# untitled.net
KiCad netlist of a schematic drawn in EAGLE
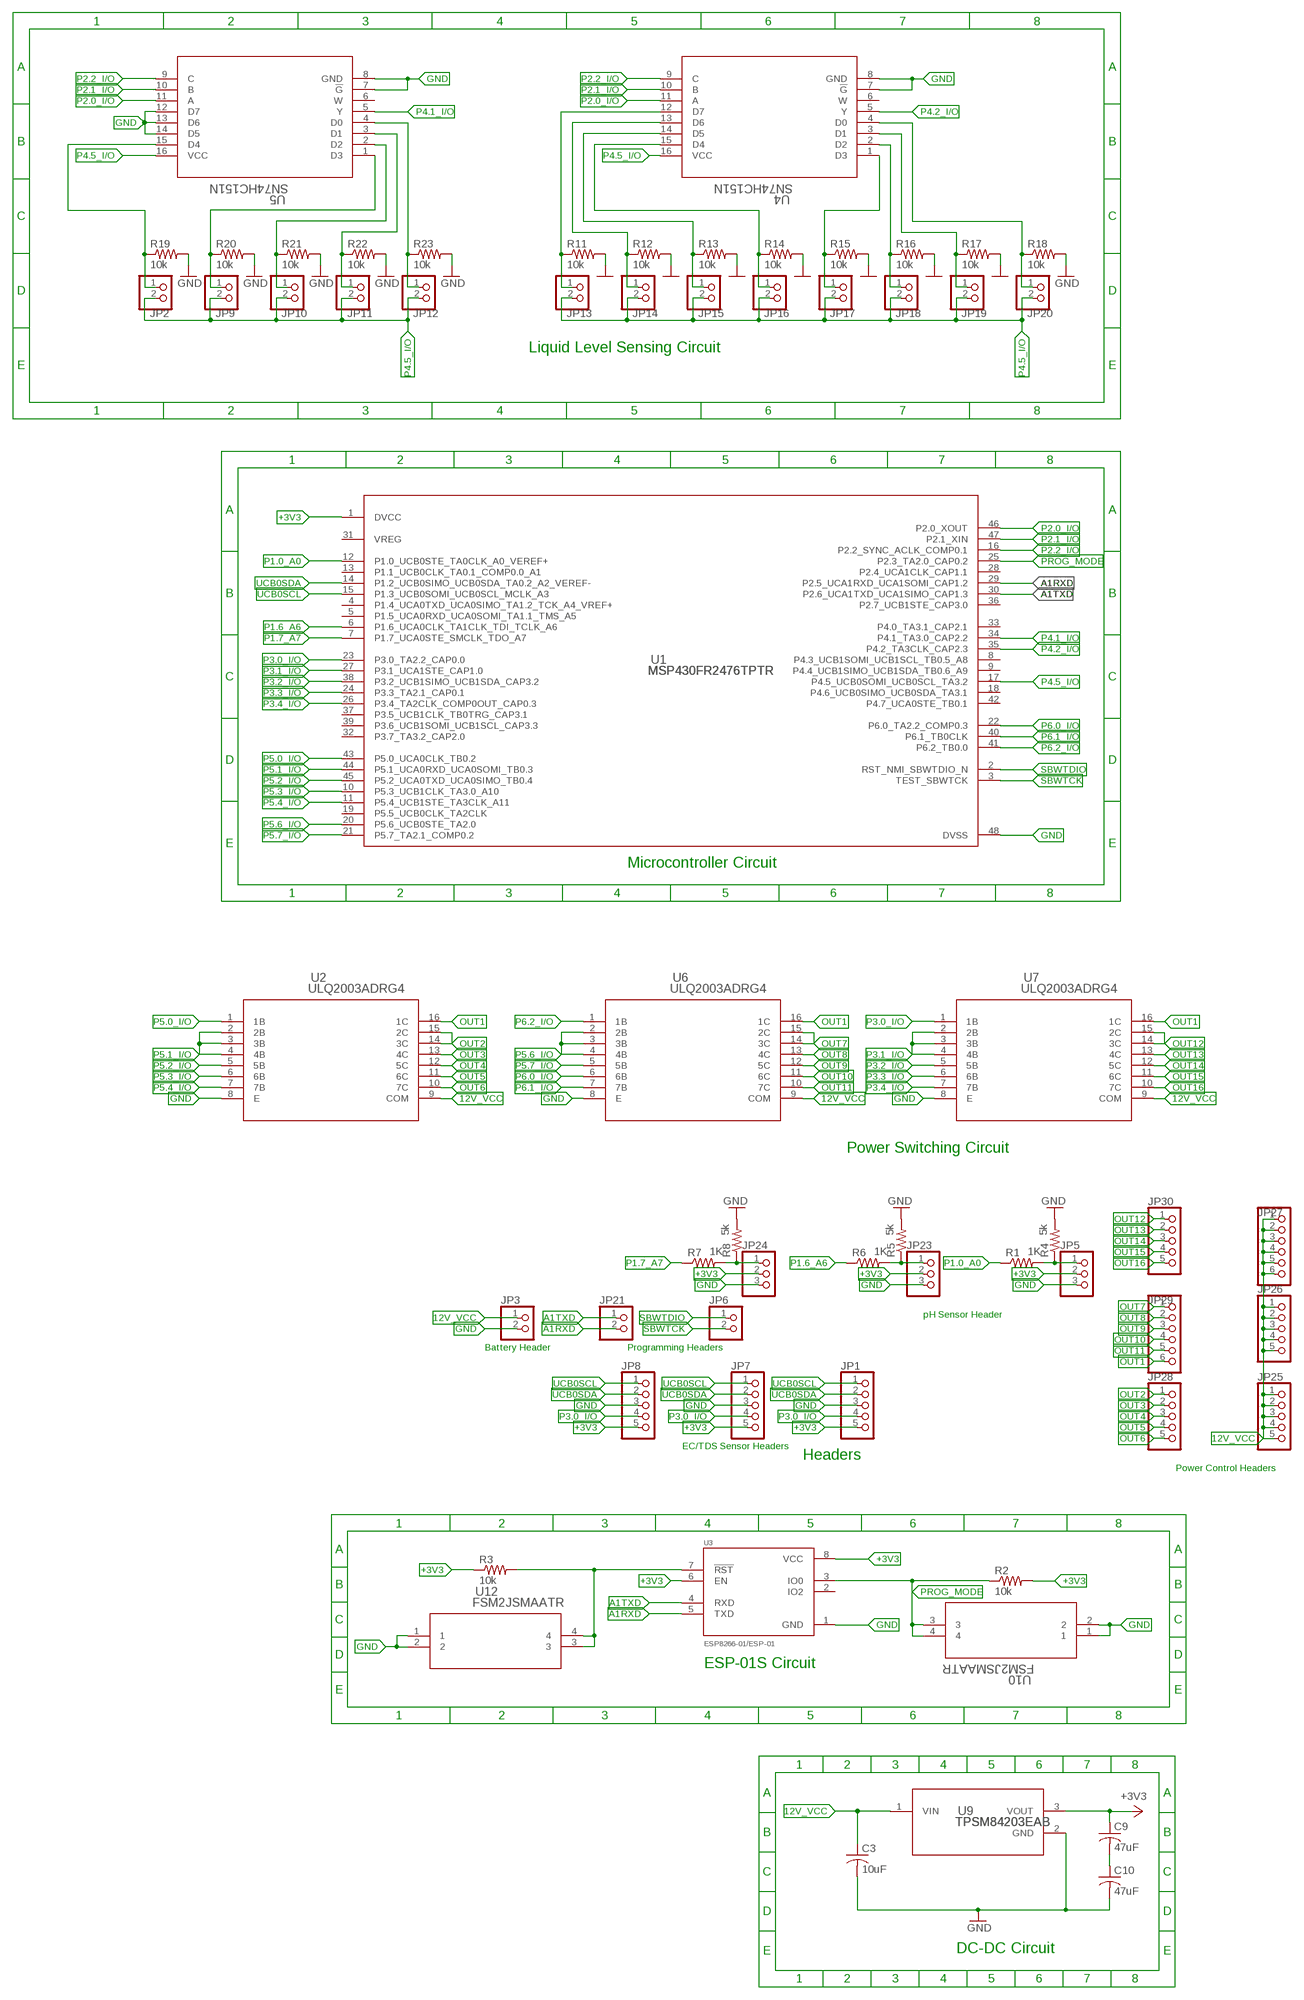
[diagram p0: schematic, sheet 1]

(export (version "E")
  (design (tool "Eeschema 10.0.6"))
  (components
    (comp (ref "C3")
      (value "10uF")
      (footprint "eagle-import:C1206")
      (libsource (lib "eagle-import") (part "C-USC1206"))
    )
    (comp (ref "C9")
      (value "47uF")
      (footprint "eagle-import:C1206")
      (libsource (lib "eagle-import") (part "C-USC1206"))
    )
    (comp (ref "C10")
      (value "47uF")
      (footprint "eagle-import:C1206")
      (libsource (lib "eagle-import") (part "C-USC1206"))
    )
    (comp (ref "JP1")
      (value "PINHD-1X5")
      (footprint "eagle-import:1X05")
      (libsource (lib "eagle-import") (part "PINHD-1X5"))
    )
    (comp (ref "JP2")
      (value "PINHD-1X2")
      (footprint "eagle-import:1X02")
      (libsource (lib "eagle-import") (part "PINHD-1X2"))
    )
    (comp (ref "JP3")
      (value "PINHD-1X2")
      (footprint "eagle-import:1X02")
      (libsource (lib "eagle-import") (part "PINHD-1X2"))
    )
    (comp (ref "JP5")
      (value "PINHD-1X3")
      (footprint "eagle-import:1X03")
      (libsource (lib "eagle-import") (part "PINHD-1X3"))
    )
    (comp (ref "JP6")
      (value "PINHD-1X2")
      (footprint "eagle-import:1X02")
      (libsource (lib "eagle-import") (part "PINHD-1X2"))
    )
    (comp (ref "JP7")
      (value "PINHD-1X5")
      (footprint "eagle-import:1X05")
      (libsource (lib "eagle-import") (part "PINHD-1X5"))
    )
    (comp (ref "JP8")
      (value "PINHD-1X5")
      (footprint "eagle-import:1X05")
      (libsource (lib "eagle-import") (part "PINHD-1X5"))
    )
    (comp (ref "JP9")
      (value "PINHD-1X2")
      (footprint "eagle-import:1X02")
      (libsource (lib "eagle-import") (part "PINHD-1X2"))
    )
    (comp (ref "JP10")
      (value "PINHD-1X2")
      (footprint "eagle-import:1X02")
      (libsource (lib "eagle-import") (part "PINHD-1X2"))
    )
    (comp (ref "JP11")
      (value "PINHD-1X2")
      (footprint "eagle-import:1X02")
      (libsource (lib "eagle-import") (part "PINHD-1X2"))
    )
    (comp (ref "JP12")
      (value "PINHD-1X2")
      (footprint "eagle-import:1X02")
      (libsource (lib "eagle-import") (part "PINHD-1X2"))
    )
    (comp (ref "JP13")
      (value "PINHD-1X2")
      (footprint "eagle-import:1X02")
      (libsource (lib "eagle-import") (part "PINHD-1X2"))
    )
    (comp (ref "JP14")
      (value "PINHD-1X2")
      (footprint "eagle-import:1X02")
      (libsource (lib "eagle-import") (part "PINHD-1X2"))
    )
    (comp (ref "JP15")
      (value "PINHD-1X2")
      (footprint "eagle-import:1X02")
      (libsource (lib "eagle-import") (part "PINHD-1X2"))
    )
    (comp (ref "JP16")
      (value "PINHD-1X2")
      (footprint "eagle-import:1X02")
      (libsource (lib "eagle-import") (part "PINHD-1X2"))
    )
    (comp (ref "JP17")
      (value "PINHD-1X2")
      (footprint "eagle-import:1X02")
      (libsource (lib "eagle-import") (part "PINHD-1X2"))
    )
    (comp (ref "JP18")
      (value "PINHD-1X2")
      (footprint "eagle-import:1X02")
      (libsource (lib "eagle-import") (part "PINHD-1X2"))
    )
    (comp (ref "JP19")
      (value "PINHD-1X2")
      (footprint "eagle-import:1X02")
      (libsource (lib "eagle-import") (part "PINHD-1X2"))
    )
    (comp (ref "JP20")
      (value "PINHD-1X2")
      (footprint "eagle-import:1X02")
      (libsource (lib "eagle-import") (part "PINHD-1X2"))
    )
    (comp (ref "JP21")
      (value "PINHD-1X2")
      (footprint "eagle-import:1X02")
      (libsource (lib "eagle-import") (part "PINHD-1X2"))
    )
    (comp (ref "JP23")
      (value "PINHD-1X3")
      (footprint "eagle-import:1X03")
      (libsource (lib "eagle-import") (part "PINHD-1X3"))
    )
    (comp (ref "JP24")
      (value "PINHD-1X3")
      (footprint "eagle-import:1X03")
      (libsource (lib "eagle-import") (part "PINHD-1X3"))
    )
    (comp (ref "JP25")
      (value "PINHD-1X5")
      (footprint "eagle-import:1X05")
      (libsource (lib "eagle-import") (part "PINHD-1X5"))
    )
    (comp (ref "JP26")
      (value "PINHD-1X5")
      (footprint "eagle-import:1X05")
      (libsource (lib "eagle-import") (part "PINHD-1X5"))
    )
    (comp (ref "JP27")
      (value "PINHD-1X6")
      (footprint "eagle-import:1X06")
      (libsource (lib "eagle-import") (part "PINHD-1X6"))
    )
    (comp (ref "JP28")
      (value "PINHD-1X5")
      (footprint "eagle-import:1X05")
      (libsource (lib "eagle-import") (part "PINHD-1X5"))
    )
    (comp (ref "JP29")
      (value "PINHD-1X6")
      (footprint "eagle-import:1X06")
      (libsource (lib "eagle-import") (part "PINHD-1X6"))
    )
    (comp (ref "JP30")
      (value "PINHD-1X5")
      (footprint "eagle-import:1X05")
      (libsource (lib "eagle-import") (part "PINHD-1X5"))
    )
    (comp (ref "R1")
      (value "1K")
      (footprint "eagle-import:R1206")
      (libsource (lib "eagle-import") (part "R-US_R1206"))
    )
    (comp (ref "R2")
      (value "10k")
      (footprint "eagle-import:R1206")
      (libsource (lib "eagle-import") (part "R-US_R1206"))
    )
    (comp (ref "R3")
      (value "10k")
      (footprint "eagle-import:R1206")
      (libsource (lib "eagle-import") (part "R-US_R1206"))
    )
    (comp (ref "R4")
      (value "5k")
      (footprint "eagle-import:R1206")
      (libsource (lib "eagle-import") (part "R-US_R1206"))
    )
    (comp (ref "R5")
      (value "5k")
      (footprint "eagle-import:R1206")
      (libsource (lib "eagle-import") (part "R-US_R1206"))
    )
    (comp (ref "R6")
      (value "1K")
      (footprint "eagle-import:R1206")
      (libsource (lib "eagle-import") (part "R-US_R1206"))
    )
    (comp (ref "R7")
      (value "1K")
      (footprint "eagle-import:R1206")
      (libsource (lib "eagle-import") (part "R-US_R1206"))
    )
    (comp (ref "R8")
      (value "5k")
      (footprint "eagle-import:R1206")
      (libsource (lib "eagle-import") (part "R-US_R1206"))
    )
    (comp (ref "R11")
      (value "10k")
      (footprint "eagle-import:R1206")
      (libsource (lib "eagle-import") (part "R-US_R1206"))
    )
    (comp (ref "R12")
      (value "10k")
      (footprint "eagle-import:R1206")
      (libsource (lib "eagle-import") (part "R-US_R1206"))
    )
    (comp (ref "R13")
      (value "10k")
      (footprint "eagle-import:R1206")
      (libsource (lib "eagle-import") (part "R-US_R1206"))
    )
    (comp (ref "R14")
      (value "10k")
      (footprint "eagle-import:R1206")
      (libsource (lib "eagle-import") (part "R-US_R1206"))
    )
    (comp (ref "R15")
      (value "10k")
      (footprint "eagle-import:R1206")
      (libsource (lib "eagle-import") (part "R-US_R1206"))
    )
    (comp (ref "R16")
      (value "10k")
      (footprint "eagle-import:R1206")
      (libsource (lib "eagle-import") (part "R-US_R1206"))
    )
    (comp (ref "R17")
      (value "10k")
      (footprint "eagle-import:R1206")
      (libsource (lib "eagle-import") (part "R-US_R1206"))
    )
    (comp (ref "R18")
      (value "10k")
      (footprint "eagle-import:R1206")
      (libsource (lib "eagle-import") (part "R-US_R1206"))
    )
    (comp (ref "R19")
      (value "10k")
      (footprint "eagle-import:R1206")
      (libsource (lib "eagle-import") (part "R-US_R1206"))
    )
    (comp (ref "R20")
      (value "10k")
      (footprint "eagle-import:R1206")
      (libsource (lib "eagle-import") (part "R-US_R1206"))
    )
    (comp (ref "R21")
      (value "10k")
      (footprint "eagle-import:R1206")
      (libsource (lib "eagle-import") (part "R-US_R1206"))
    )
    (comp (ref "R22")
      (value "10k")
      (footprint "eagle-import:R1206")
      (libsource (lib "eagle-import") (part "R-US_R1206"))
    )
    (comp (ref "R23")
      (value "10k")
      (footprint "eagle-import:R1206")
      (libsource (lib "eagle-import") (part "R-US_R1206"))
    )
    (comp (ref "U1")
      (value "MSP430FR2476TPTR")
      (footprint "eagle-import:PT0048A_N")
      (fields (field (name "COPYRIGHT") "Copyright (C) 2023 Ultra Librarian. All rights reserved."))
      (libsource (lib "eagle-import") (part "MSP430FR2476TPTR"))
    )
    (comp (ref "U2")
      (value "ULQ2003ADRG4")
      (footprint "eagle-import:D16")
      (fields (field (name "COPYRIGHT") "Copyright (C) 2023 Ultra Librarian. All rights reserved."))
      (libsource (lib "eagle-import") (part "ULQ2003ADRG4"))
    )
    (comp (ref "U3")
      (value "ESP8266-01/ESP-01")
      (footprint "eagle-import:XCVR_ESP8266-01_ESP-01")
      (fields (field (name "MF") "AI-Thinker"))
      (libsource (lib "eagle-import") (part "ESP8266-01/ESP-01"))
    )
    (comp (ref "U4")
      (value "SN74HC151N")
      (footprint "eagle-import:N16")
      (fields (field (name "COPYRIGHT") "Copyright (C) 2022 Ultra Librarian. All rights reserved."))
      (libsource (lib "eagle-import") (part "SN74HC151N"))
    )
    (comp (ref "U5")
      (value "SN74HC151N")
      (footprint "eagle-import:N16")
      (fields (field (name "COPYRIGHT") "Copyright (C) 2022 Ultra Librarian. All rights reserved."))
      (libsource (lib "eagle-import") (part "SN74HC151N"))
    )
    (comp (ref "U6")
      (value "ULQ2003ADRG4")
      (footprint "eagle-import:D16")
      (fields
        (field (name "SPICEPREFIX") "X")
        (field (name "COPYRIGHT") "Copyright (C) 2023 Ultra Librarian. All rights reserved.")
      )
      (libsource (lib "eagle-import") (part "ULQ2003ADRG4"))
    )
    (comp (ref "U7")
      (value "ULQ2003ADRG4")
      (footprint "eagle-import:D16")
      (fields
        (field (name "SPICEPREFIX") "X")
        (field (name "COPYRIGHT") "Copyright (C) 2023 Ultra Librarian. All rights reserved.")
      )
      (libsource (lib "eagle-import") (part "ULQ2003ADRG4"))
    )
    (comp (ref "U9")
      (value "TPSM84203EAB")
      (footprint "eagle-import:EAB0003A")
      (fields (field (name "COPYRIGHT") "Copyright (C) 2023 Ultra Librarian. All rights reserved."))
      (libsource (lib "eagle-import") (part "TPSM84203EAB"))
    )
    (comp (ref "U10")
      (value "FSM2JSMAATR")
      (footprint "eagle-import:SWITCH_FSM2JSMAA_TYC")
      (fields (field (name "COPYRIGHT") "Copyright (C) 2023 Ultra Librarian. All rights reserved."))
      (libsource (lib "eagle-import") (part "FSM2JSMAATR"))
    )
    (comp (ref "U12")
      (value "FSM2JSMAATR")
      (footprint "eagle-import:SWITCH_FSM2JSMAA_TYC")
      (fields (field (name "COPYRIGHT") "Copyright (C) 2023 Ultra Librarian. All rights reserved."))
      (libsource (lib "eagle-import") (part "FSM2JSMAATR"))
    )
  )
  (nets
    (net (code "1") (name "+3V3") (class "Default")
      (node (ref "C9") (pin "1") (pinfunction "1_1") (pintype "passive"))
      (node (ref "JP1") (pin "5") (pinfunction "5_5") (pintype "passive"))
      (node (ref "JP23") (pin "2") (pinfunction "2_2") (pintype "passive"))
      (node (ref "JP24") (pin "2") (pinfunction "2_2") (pintype "passive"))
      (node (ref "JP5") (pin "2") (pinfunction "2_2") (pintype "passive"))
      (node (ref "JP7") (pin "5") (pinfunction "5_5") (pintype "passive"))
      (node (ref "JP8") (pin "5") (pinfunction "5_5") (pintype "passive"))
      (node (ref "R2") (pin "2") (pinfunction "2_2") (pintype "passive"))
      (node (ref "R3") (pin "1") (pinfunction "1_1") (pintype "passive"))
      (node (ref "U1") (pin "1") (pinfunction "DVCC_1") (pintype "power_in"))
      (node (ref "U3") (pin "6") (pinfunction "EN_6") (pintype "input"))
      (node (ref "U3") (pin "8") (pinfunction "VCC_8") (pintype "power_in"))
      (node (ref "U9") (pin "3") (pinfunction "VOUT_3") (pintype "power_in"))
    )
    (net (code "2") (name "12V_VCC") (class "Default")
      (node (ref "C3") (pin "1") (pinfunction "1_1") (pintype "passive"))
      (node (ref "JP25") (pin "1") (pinfunction "1_1") (pintype "passive"))
      (node (ref "JP25") (pin "2") (pinfunction "2_2") (pintype "passive"))
      (node (ref "JP25") (pin "3") (pinfunction "3_3") (pintype "passive"))
      (node (ref "JP25") (pin "4") (pinfunction "4_4") (pintype "passive"))
      (node (ref "JP25") (pin "5") (pinfunction "5_5") (pintype "passive"))
      (node (ref "JP26") (pin "1") (pinfunction "1_1") (pintype "passive"))
      (node (ref "JP26") (pin "2") (pinfunction "2_2") (pintype "passive"))
      (node (ref "JP26") (pin "3") (pinfunction "3_3") (pintype "passive"))
      (node (ref "JP26") (pin "4") (pinfunction "4_4") (pintype "passive"))
      (node (ref "JP26") (pin "5") (pinfunction "5_5") (pintype "passive"))
      (node (ref "JP27") (pin "1") (pinfunction "1_1") (pintype "passive"))
      (node (ref "JP27") (pin "2") (pinfunction "2_2") (pintype "passive"))
      (node (ref "JP27") (pin "3") (pinfunction "3_3") (pintype "passive"))
      (node (ref "JP27") (pin "4") (pinfunction "4_4") (pintype "passive"))
      (node (ref "JP27") (pin "5") (pinfunction "5_5") (pintype "passive"))
      (node (ref "JP27") (pin "6") (pinfunction "6_6") (pintype "passive"))
      (node (ref "JP3") (pin "1") (pinfunction "1_1") (pintype "passive"))
      (node (ref "U2") (pin "9") (pinfunction "COM_9") (pintype "input"))
      (node (ref "U6") (pin "9") (pinfunction "COM_9") (pintype "input"))
      (node (ref "U7") (pin "9") (pinfunction "COM_9") (pintype "input"))
      (node (ref "U9") (pin "1") (pinfunction "VIN_1") (pintype "power_in"))
    )
    (net (code "3") (name "A1RXD") (class "Default")
      (node (ref "JP21") (pin "2") (pinfunction "2_2") (pintype "passive"))
      (node (ref "U1") (pin "29") (pinfunction "P2.5_UCA1RXD_UCA1SOMI_CAP1.2_29") (pintype "bidirectional"))
      (node (ref "U3") (pin "5") (pinfunction "TXD_5") (pintype "output"))
    )
    (net (code "4") (name "A1TXD") (class "Default")
      (node (ref "JP21") (pin "1") (pinfunction "1_1") (pintype "passive"))
      (node (ref "U1") (pin "30") (pinfunction "P2.6_UCA1TXD_UCA1SIMO_CAP1.3_30") (pintype "bidirectional"))
      (node (ref "U3") (pin "4") (pinfunction "RXD_4") (pintype "input"))
    )
    (net (code "5") (name "GND") (class "Default")
      (node (ref "C10") (pin "2") (pinfunction "2_2") (pintype "passive"))
      (node (ref "C3") (pin "2") (pinfunction "2_2") (pintype "passive"))
      (node (ref "JP1") (pin "3") (pinfunction "3_3") (pintype "passive"))
      (node (ref "JP23") (pin "3") (pinfunction "3_3") (pintype "passive"))
      (node (ref "JP24") (pin "3") (pinfunction "3_3") (pintype "passive"))
      (node (ref "JP3") (pin "2") (pinfunction "2_2") (pintype "passive"))
      (node (ref "JP5") (pin "3") (pinfunction "3_3") (pintype "passive"))
      (node (ref "JP7") (pin "3") (pinfunction "3_3") (pintype "passive"))
      (node (ref "JP8") (pin "3") (pinfunction "3_3") (pintype "passive"))
      (node (ref "R11") (pin "2") (pinfunction "2_2") (pintype "passive"))
      (node (ref "R12") (pin "2") (pinfunction "2_2") (pintype "passive"))
      (node (ref "R13") (pin "2") (pinfunction "2_2") (pintype "passive"))
      (node (ref "R14") (pin "2") (pinfunction "2_2") (pintype "passive"))
      (node (ref "R15") (pin "2") (pinfunction "2_2") (pintype "passive"))
      (node (ref "R16") (pin "2") (pinfunction "2_2") (pintype "passive"))
      (node (ref "R17") (pin "2") (pinfunction "2_2") (pintype "passive"))
      (node (ref "R18") (pin "2") (pinfunction "2_2") (pintype "passive"))
      (node (ref "R19") (pin "2") (pinfunction "2_2") (pintype "passive"))
      (node (ref "R20") (pin "2") (pinfunction "2_2") (pintype "passive"))
      (node (ref "R21") (pin "2") (pinfunction "2_2") (pintype "passive"))
      (node (ref "R22") (pin "2") (pinfunction "2_2") (pintype "passive"))
      (node (ref "R23") (pin "2") (pinfunction "2_2") (pintype "passive"))
      (node (ref "R4") (pin "2") (pinfunction "2_2") (pintype "passive"))
      (node (ref "R5") (pin "2") (pinfunction "2_2") (pintype "passive"))
      (node (ref "R8") (pin "2") (pinfunction "2_2") (pintype "passive"))
      (node (ref "U1") (pin "48") (pinfunction "DVSS_48") (pintype "power_in"))
      (node (ref "U10") (pin "1") (pinfunction "1_1") (pintype "passive"))
      (node (ref "U10") (pin "2") (pinfunction "2_2") (pintype "passive"))
      (node (ref "U12") (pin "1") (pinfunction "1_1") (pintype "passive"))
      (node (ref "U12") (pin "2") (pinfunction "2_2") (pintype "passive"))
      (node (ref "U2") (pin "8") (pinfunction "E_8") (pintype "passive"))
      (node (ref "U3") (pin "1") (pinfunction "GND_1") (pintype "power_in"))
      (node (ref "U4") (pin "7") (pinfunction "~{G}_7") (pintype "input"))
      (node (ref "U4") (pin "8") (pinfunction "GND_8") (pintype "power_in"))
      (node (ref "U5") (pin "12") (pinfunction "D7_12") (pintype "input"))
      (node (ref "U5") (pin "13") (pinfunction "D6_13") (pintype "input"))
      (node (ref "U5") (pin "14") (pinfunction "D5_14") (pintype "input"))
      (node (ref "U5") (pin "7") (pinfunction "~{G}_7") (pintype "input"))
      (node (ref "U5") (pin "8") (pinfunction "GND_8") (pintype "power_in"))
      (node (ref "U6") (pin "8") (pinfunction "E_8") (pintype "passive"))
      (node (ref "U7") (pin "8") (pinfunction "E_8") (pintype "passive"))
      (node (ref "U9") (pin "2") (pinfunction "GND_2") (pintype "power_in"))
    )
    (net (code "6") (name "Net-(C10-Pad1)") (class "Default")
      (node (ref "C10") (pin "1") (pinfunction "1_1") (pintype "passive"))
      (node (ref "C9") (pin "2") (pinfunction "2_2") (pintype "passive"))
    )
    (net (code "7") (name "Net-(JP5-Pad1)") (class "Default")
      (node (ref "JP5") (pin "1") (pinfunction "1_1") (pintype "passive"))
      (node (ref "R1") (pin "2") (pinfunction "2_2") (pintype "passive"))
      (node (ref "R4") (pin "1") (pinfunction "1_1") (pintype "passive"))
    )
    (net (code "8") (name "Net-(JP23-Pad1)") (class "Default")
      (node (ref "JP23") (pin "1") (pinfunction "1_1") (pintype "passive"))
      (node (ref "R5") (pin "1") (pinfunction "1_1") (pintype "passive"))
      (node (ref "R6") (pin "2") (pinfunction "2_2") (pintype "passive"))
    )
    (net (code "9") (name "Net-(JP24-Pad1)") (class "Default")
      (node (ref "JP24") (pin "1") (pinfunction "1_1") (pintype "passive"))
      (node (ref "R7") (pin "2") (pinfunction "2_2") (pintype "passive"))
      (node (ref "R8") (pin "1") (pinfunction "1_1") (pintype "passive"))
    )
    (net (code "10") (name "Net-(U3-~{RST})") (class "Default")
      (node (ref "R3") (pin "2") (pinfunction "2_2") (pintype "passive"))
      (node (ref "U12") (pin "3") (pinfunction "3_3") (pintype "passive"))
      (node (ref "U12") (pin "4") (pinfunction "4_4") (pintype "passive"))
      (node (ref "U3") (pin "7") (pinfunction "~{RST}_7") (pintype "input"))
    )
    (net (code "11") (name "Net-(U4-D0)") (class "Default")
      (node (ref "JP20") (pin "1") (pinfunction "1_1") (pintype "passive"))
      (node (ref "R18") (pin "1") (pinfunction "1_1") (pintype "passive"))
      (node (ref "U4") (pin "4") (pinfunction "D0_4") (pintype "input"))
    )
    (net (code "12") (name "Net-(U4-D1)") (class "Default")
      (node (ref "JP19") (pin "1") (pinfunction "1_1") (pintype "passive"))
      (node (ref "R17") (pin "1") (pinfunction "1_1") (pintype "passive"))
      (node (ref "U4") (pin "3") (pinfunction "D1_3") (pintype "input"))
    )
    (net (code "13") (name "Net-(U4-D2)") (class "Default")
      (node (ref "JP18") (pin "1") (pinfunction "1_1") (pintype "passive"))
      (node (ref "R16") (pin "1") (pinfunction "1_1") (pintype "passive"))
      (node (ref "U4") (pin "2") (pinfunction "D2_2") (pintype "input"))
    )
    (net (code "14") (name "Net-(U4-D3)") (class "Default")
      (node (ref "JP17") (pin "1") (pinfunction "1_1") (pintype "passive"))
      (node (ref "R15") (pin "1") (pinfunction "1_1") (pintype "passive"))
      (node (ref "U4") (pin "1") (pinfunction "D3_1") (pintype "input"))
    )
    (net (code "15") (name "Net-(U4-D4)") (class "Default")
      (node (ref "JP16") (pin "1") (pinfunction "1_1") (pintype "passive"))
      (node (ref "R14") (pin "1") (pinfunction "1_1") (pintype "passive"))
      (node (ref "U4") (pin "15") (pinfunction "D4_15") (pintype "input"))
    )
    (net (code "16") (name "Net-(U4-D5)") (class "Default")
      (node (ref "JP15") (pin "1") (pinfunction "1_1") (pintype "passive"))
      (node (ref "R13") (pin "1") (pinfunction "1_1") (pintype "passive"))
      (node (ref "U4") (pin "14") (pinfunction "D5_14") (pintype "input"))
    )
    (net (code "17") (name "Net-(U4-D6)") (class "Default")
      (node (ref "JP14") (pin "1") (pinfunction "1_1") (pintype "passive"))
      (node (ref "R12") (pin "1") (pinfunction "1_1") (pintype "passive"))
      (node (ref "U4") (pin "13") (pinfunction "D6_13") (pintype "input"))
    )
    (net (code "18") (name "Net-(U4-D7)") (class "Default")
      (node (ref "JP13") (pin "1") (pinfunction "1_1") (pintype "passive"))
      (node (ref "R11") (pin "1") (pinfunction "1_1") (pintype "passive"))
      (node (ref "U4") (pin "12") (pinfunction "D7_12") (pintype "input"))
    )
    (net (code "19") (name "Net-(U5-D0)") (class "Default")
      (node (ref "JP12") (pin "1") (pinfunction "1_1") (pintype "passive"))
      (node (ref "R23") (pin "1") (pinfunction "1_1") (pintype "passive"))
      (node (ref "U5") (pin "4") (pinfunction "D0_4") (pintype "input"))
    )
    (net (code "20") (name "Net-(U5-D1)") (class "Default")
      (node (ref "JP11") (pin "1") (pinfunction "1_1") (pintype "passive"))
      (node (ref "R22") (pin "1") (pinfunction "1_1") (pintype "passive"))
      (node (ref "U5") (pin "3") (pinfunction "D1_3") (pintype "input"))
    )
    (net (code "21") (name "Net-(U5-D2)") (class "Default")
      (node (ref "JP10") (pin "1") (pinfunction "1_1") (pintype "passive"))
      (node (ref "R21") (pin "1") (pinfunction "1_1") (pintype "passive"))
      (node (ref "U5") (pin "2") (pinfunction "D2_2") (pintype "input"))
    )
    (net (code "22") (name "Net-(U5-D3)") (class "Default")
      (node (ref "JP9") (pin "1") (pinfunction "1_1") (pintype "passive"))
      (node (ref "R20") (pin "1") (pinfunction "1_1") (pintype "passive"))
      (node (ref "U5") (pin "1") (pinfunction "D3_1") (pintype "input"))
    )
    (net (code "23") (name "Net-(U5-D4)") (class "Default")
      (node (ref "JP2") (pin "1") (pinfunction "1_1") (pintype "passive"))
      (node (ref "R19") (pin "1") (pinfunction "1_1") (pintype "passive"))
      (node (ref "U5") (pin "15") (pinfunction "D4_15") (pintype "input"))
    )
    (net (code "24") (name "OUT1") (class "Default")
      (node (ref "JP29") (pin "6") (pinfunction "6_6") (pintype "passive"))
      (node (ref "U2") (pin "16") (pinfunction "1C_16") (pintype "passive"))
      (node (ref "U6") (pin "16") (pinfunction "1C_16") (pintype "passive"))
      (node (ref "U7") (pin "16") (pinfunction "1C_16") (pintype "passive"))
    )
    (net (code "25") (name "OUT2") (class "Default")
      (node (ref "JP28") (pin "1") (pinfunction "1_1") (pintype "passive"))
      (node (ref "U2") (pin "14") (pinfunction "3C_14") (pintype "passive"))
      (node (ref "U2") (pin "15") (pinfunction "2C_15") (pintype "passive"))
    )
    (net (code "26") (name "OUT3") (class "Default")
      (node (ref "JP28") (pin "2") (pinfunction "2_2") (pintype "passive"))
      (node (ref "U2") (pin "13") (pinfunction "4C_13") (pintype "passive"))
    )
    (net (code "27") (name "OUT4") (class "Default")
      (node (ref "JP28") (pin "3") (pinfunction "3_3") (pintype "passive"))
      (node (ref "U2") (pin "12") (pinfunction "5C_12") (pintype "passive"))
    )
    (net (code "28") (name "OUT5") (class "Default")
      (node (ref "JP28") (pin "4") (pinfunction "4_4") (pintype "passive"))
      (node (ref "U2") (pin "11") (pinfunction "6C_11") (pintype "passive"))
    )
    (net (code "29") (name "OUT6") (class "Default")
      (node (ref "JP28") (pin "5") (pinfunction "5_5") (pintype "passive"))
      (node (ref "U2") (pin "10") (pinfunction "7C_10") (pintype "passive"))
    )
    (net (code "30") (name "OUT7") (class "Default")
      (node (ref "JP29") (pin "1") (pinfunction "1_1") (pintype "passive"))
      (node (ref "U6") (pin "14") (pinfunction "3C_14") (pintype "passive"))
      (node (ref "U6") (pin "15") (pinfunction "2C_15") (pintype "passive"))
    )
    (net (code "31") (name "OUT8") (class "Default")
      (node (ref "JP29") (pin "2") (pinfunction "2_2") (pintype "passive"))
      (node (ref "U6") (pin "13") (pinfunction "4C_13") (pintype "passive"))
    )
    (net (code "32") (name "OUT9") (class "Default")
      (node (ref "JP29") (pin "3") (pinfunction "3_3") (pintype "passive"))
      (node (ref "U6") (pin "12") (pinfunction "5C_12") (pintype "passive"))
    )
    (net (code "33") (name "OUT10") (class "Default")
      (node (ref "JP29") (pin "4") (pinfunction "4_4") (pintype "passive"))
      (node (ref "U6") (pin "11") (pinfunction "6C_11") (pintype "passive"))
    )
    (net (code "34") (name "OUT11") (class "Default")
      (node (ref "JP29") (pin "5") (pinfunction "5_5") (pintype "passive"))
      (node (ref "U6") (pin "10") (pinfunction "7C_10") (pintype "passive"))
    )
    (net (code "35") (name "OUT12") (class "Default")
      (node (ref "JP30") (pin "1") (pinfunction "1_1") (pintype "passive"))
      (node (ref "U7") (pin "14") (pinfunction "3C_14") (pintype "passive"))
      (node (ref "U7") (pin "15") (pinfunction "2C_15") (pintype "passive"))
    )
    (net (code "36") (name "OUT13") (class "Default")
      (node (ref "JP30") (pin "2") (pinfunction "2_2") (pintype "passive"))
      (node (ref "U7") (pin "13") (pinfunction "4C_13") (pintype "passive"))
    )
    (net (code "37") (name "OUT14") (class "Default")
      (node (ref "JP30") (pin "3") (pinfunction "3_3") (pintype "passive"))
      (node (ref "U7") (pin "12") (pinfunction "5C_12") (pintype "passive"))
    )
    (net (code "38") (name "OUT15") (class "Default")
      (node (ref "JP30") (pin "4") (pinfunction "4_4") (pintype "passive"))
      (node (ref "U7") (pin "11") (pinfunction "6C_11") (pintype "passive"))
    )
    (net (code "39") (name "OUT16") (class "Default")
      (node (ref "JP30") (pin "5") (pinfunction "5_5") (pintype "passive"))
      (node (ref "U7") (pin "10") (pinfunction "7C_10") (pintype "passive"))
    )
    (net (code "40") (name "P1.0_A0") (class "Default")
      (node (ref "R1") (pin "1") (pinfunction "1_1") (pintype "passive"))
      (node (ref "U1") (pin "12") (pinfunction "P1.0_UCB0STE_TA0CLK_A0_VEREF+_12") (pintype "bidirectional"))
    )
    (net (code "41") (name "P1.6_A6") (class "Default")
      (node (ref "R6") (pin "1") (pinfunction "1_1") (pintype "passive"))
      (node (ref "U1") (pin "6") (pinfunction "P1.6_UCA0CLK_TA1CLK_TDI_TCLK_A6_6") (pintype "bidirectional"))
    )
    (net (code "42") (name "P1.7_A7") (class "Default")
      (node (ref "R7") (pin "1") (pinfunction "1_1") (pintype "passive"))
      (node (ref "U1") (pin "7") (pinfunction "P1.7_UCA0STE_SMCLK_TDO_A7_7") (pintype "bidirectional"))
    )
    (net (code "43") (name "P2.0_I{slash}O") (class "Default")
      (node (ref "U1") (pin "46") (pinfunction "P2.0_XOUT_46") (pintype "bidirectional"))
      (node (ref "U4") (pin "11") (pinfunction "A_11") (pintype "input"))
      (node (ref "U5") (pin "11") (pinfunction "A_11") (pintype "input"))
    )
    (net (code "44") (name "P2.1_I{slash}O") (class "Default")
      (node (ref "U1") (pin "47") (pinfunction "P2.1_XIN_47") (pintype "bidirectional"))
      (node (ref "U4") (pin "10") (pinfunction "B_10") (pintype "input"))
      (node (ref "U5") (pin "10") (pinfunction "B_10") (pintype "input"))
    )
    (net (code "45") (name "P2.2_I{slash}O") (class "Default")
      (node (ref "U1") (pin "16") (pinfunction "P2.2_SYNC_ACLK_COMP0.1_16") (pintype "bidirectional"))
      (node (ref "U4") (pin "9") (pinfunction "C_9") (pintype "input"))
      (node (ref "U5") (pin "9") (pinfunction "C_9") (pintype "input"))
    )
    (net (code "46") (name "P3.0_I{slash}O") (class "Default")
      (node (ref "JP1") (pin "4") (pinfunction "4_4") (pintype "passive"))
      (node (ref "JP7") (pin "4") (pinfunction "4_4") (pintype "passive"))
      (node (ref "JP8") (pin "4") (pinfunction "4_4") (pintype "passive"))
      (node (ref "U1") (pin "23") (pinfunction "P3.0_TA2.2_CAP0.0_23") (pintype "bidirectional"))
      (node (ref "U7") (pin "1") (pinfunction "1B_1") (pintype "input"))
    )
    (net (code "47") (name "P3.1_I{slash}O") (class "Default")
      (node (ref "U1") (pin "27") (pinfunction "P3.1_UCA1STE_CAP1.0_27") (pintype "bidirectional"))
      (node (ref "U7") (pin "2") (pinfunction "2B_2") (pintype "input"))
      (node (ref "U7") (pin "3") (pinfunction "3B_3") (pintype "input"))
      (node (ref "U7") (pin "4") (pinfunction "4B_4") (pintype "input"))
    )
    (net (code "48") (name "P3.2_I{slash}O") (class "Default")
      (node (ref "U1") (pin "38") (pinfunction "P3.2_UCB1SIMO_UCB1SDA_CAP3.2_38") (pintype "bidirectional"))
      (node (ref "U7") (pin "5") (pinfunction "5B_5") (pintype "input"))
    )
    (net (code "49") (name "P3.3_I{slash}O") (class "Default")
      (node (ref "U1") (pin "24") (pinfunction "P3.3_TA2.1_CAP0.1_24") (pintype "bidirectional"))
      (node (ref "U7") (pin "6") (pinfunction "6B_6") (pintype "input"))
    )
    (net (code "50") (name "P3.4_I{slash}O") (class "Default")
      (node (ref "U1") (pin "26") (pinfunction "P3.4_TA2CLK_COMP0OUT_CAP0.3_26") (pintype "bidirectional"))
      (node (ref "U7") (pin "7") (pinfunction "7B_7") (pintype "input"))
    )
    (net (code "51") (name "P4.1_I{slash}O") (class "Default")
      (node (ref "U1") (pin "34") (pinfunction "P4.1_TA3.0_CAP2.2_34") (pintype "bidirectional"))
      (node (ref "U5") (pin "5") (pinfunction "Y_5") (pintype "output"))
    )
    (net (code "52") (name "P4.2_I{slash}O") (class "Default")
      (node (ref "U1") (pin "35") (pinfunction "P4.2_TA3CLK_CAP2.3_35") (pintype "bidirectional"))
      (node (ref "U4") (pin "5") (pinfunction "Y_5") (pintype "output"))
    )
    (net (code "53") (name "P4.5_I{slash}O") (class "Default")
      (node (ref "JP10") (pin "2") (pinfunction "2_2") (pintype "passive"))
      (node (ref "JP11") (pin "2") (pinfunction "2_2") (pintype "passive"))
      (node (ref "JP12") (pin "2") (pinfunction "2_2") (pintype "passive"))
      (node (ref "JP13") (pin "2") (pinfunction "2_2") (pintype "passive"))
      (node (ref "JP14") (pin "2") (pinfunction "2_2") (pintype "passive"))
      (node (ref "JP15") (pin "2") (pinfunction "2_2") (pintype "passive"))
      (node (ref "JP16") (pin "2") (pinfunction "2_2") (pintype "passive"))
      (node (ref "JP17") (pin "2") (pinfunction "2_2") (pintype "passive"))
      (node (ref "JP18") (pin "2") (pinfunction "2_2") (pintype "passive"))
      (node (ref "JP19") (pin "2") (pinfunction "2_2") (pintype "passive"))
      (node (ref "JP2") (pin "2") (pinfunction "2_2") (pintype "passive"))
      (node (ref "JP20") (pin "2") (pinfunction "2_2") (pintype "passive"))
      (node (ref "JP9") (pin "2") (pinfunction "2_2") (pintype "passive"))
      (node (ref "U1") (pin "17") (pinfunction "P4.5_UCB0SOMI_UCB0SCL_TA3.2_17") (pintype "bidirectional"))
      (node (ref "U4") (pin "16") (pinfunction "VCC_16") (pintype "power_in"))
      (node (ref "U5") (pin "16") (pinfunction "VCC_16") (pintype "power_in"))
    )
    (net (code "54") (name "P5.0_I{slash}O") (class "Default")
      (node (ref "U1") (pin "43") (pinfunction "P5.0_UCA0CLK_TB0.2_43") (pintype "bidirectional"))
      (node (ref "U2") (pin "1") (pinfunction "1B_1") (pintype "input"))
    )
    (net (code "55") (name "P5.1_I{slash}O") (class "Default")
      (node (ref "U1") (pin "44") (pinfunction "P5.1_UCA0RXD_UCA0SOMI_TB0.3_44") (pintype "bidirectional"))
      (node (ref "U2") (pin "2") (pinfunction "2B_2") (pintype "input"))
      (node (ref "U2") (pin "3") (pinfunction "3B_3") (pintype "input"))
      (node (ref "U2") (pin "4") (pinfunction "4B_4") (pintype "input"))
    )
    (net (code "56") (name "P5.2_I{slash}O") (class "Default")
      (node (ref "U1") (pin "45") (pinfunction "P5.2_UCA0TXD_UCA0SIMO_TB0.4_45") (pintype "bidirectional"))
      (node (ref "U2") (pin "5") (pinfunction "5B_5") (pintype "input"))
    )
    (net (code "57") (name "P5.3_I{slash}O") (class "Default")
      (node (ref "U1") (pin "10") (pinfunction "P5.3_UCB1CLK_TA3.0_A10_10") (pintype "bidirectional"))
      (node (ref "U2") (pin "6") (pinfunction "6B_6") (pintype "input"))
    )
    (net (code "58") (name "P5.4_I{slash}O") (class "Default")
      (node (ref "U1") (pin "11") (pinfunction "P5.4_UCB1STE_TA3CLK_A11_11") (pintype "bidirectional"))
      (node (ref "U2") (pin "7") (pinfunction "7B_7") (pintype "input"))
    )
    (net (code "59") (name "P5.6_I{slash}O") (class "Default")
      (node (ref "U1") (pin "20") (pinfunction "P5.6_UCB0STE_TA2.0_20") (pintype "bidirectional"))
      (node (ref "U6") (pin "2") (pinfunction "2B_2") (pintype "input"))
      (node (ref "U6") (pin "3") (pinfunction "3B_3") (pintype "input"))
      (node (ref "U6") (pin "4") (pinfunction "4B_4") (pintype "input"))
    )
    (net (code "60") (name "P5.7_I{slash}O") (class "Default")
      (node (ref "U1") (pin "21") (pinfunction "P5.7_TA2.1_COMP0.2_21") (pintype "bidirectional"))
      (node (ref "U6") (pin "5") (pinfunction "5B_5") (pintype "input"))
    )
    (net (code "61") (name "P6.0_I{slash}O") (class "Default")
      (node (ref "U1") (pin "22") (pinfunction "P6.0_TA2.2_COMP0.3_22") (pintype "bidirectional"))
      (node (ref "U6") (pin "6") (pinfunction "6B_6") (pintype "input"))
    )
    (net (code "62") (name "P6.1_I{slash}O") (class "Default")
      (node (ref "U1") (pin "40") (pinfunction "P6.1_TB0CLK_40") (pintype "bidirectional"))
      (node (ref "U6") (pin "7") (pinfunction "7B_7") (pintype "input"))
    )
    (net (code "63") (name "P6.2_I{slash}O") (class "Default")
      (node (ref "U1") (pin "41") (pinfunction "P6.2_TB0.0_41") (pintype "bidirectional"))
      (node (ref "U6") (pin "1") (pinfunction "1B_1") (pintype "input"))
    )
    (net (code "64") (name "PROG_MODE") (class "Default")
      (node (ref "R2") (pin "1") (pinfunction "1_1") (pintype "passive"))
      (node (ref "U1") (pin "25") (pinfunction "P2.3_TA2.0_CAP0.2_25") (pintype "bidirectional"))
      (node (ref "U10") (pin "3") (pinfunction "3_3") (pintype "passive"))
      (node (ref "U10") (pin "4") (pinfunction "4_4") (pintype "passive"))
      (node (ref "U3") (pin "3") (pinfunction "IO0_3") (pintype "bidirectional"))
    )
    (net (code "65") (name "SBWTCK") (class "Default")
      (node (ref "JP6") (pin "2") (pinfunction "2_2") (pintype "passive"))
      (node (ref "U1") (pin "3") (pinfunction "TEST_SBWTCK_3") (pintype "input"))
    )
    (net (code "66") (name "SBWTDIO") (class "Default")
      (node (ref "JP6") (pin "1") (pinfunction "1_1") (pintype "passive"))
      (node (ref "U1") (pin "2") (pinfunction "RST_NMI_SBWTDIO_N_2") (pintype "bidirectional"))
    )
    (net (code "67") (name "UCB0SCL") (class "Default")
      (node (ref "JP1") (pin "1") (pinfunction "1_1") (pintype "passive"))
      (node (ref "JP7") (pin "1") (pinfunction "1_1") (pintype "passive"))
      (node (ref "JP8") (pin "1") (pinfunction "1_1") (pintype "passive"))
      (node (ref "U1") (pin "15") (pinfunction "P1.3_UCB0SOMI_UCB0SCL_MCLK_A3_15") (pintype "bidirectional"))
    )
    (net (code "68") (name "UCB0SDA") (class "Default")
      (node (ref "JP1") (pin "2") (pinfunction "2_2") (pintype "passive"))
      (node (ref "JP7") (pin "2") (pinfunction "2_2") (pintype "passive"))
      (node (ref "JP8") (pin "2") (pinfunction "2_2") (pintype "passive"))
      (node (ref "U1") (pin "14") (pinfunction "P1.2_UCB0SIMO_UCB0SDA_TA0.2_A2_VEREF-_14") (pintype "bidirectional"))
    )
    (net (code "69") (name "unconnected-(U1-P1.1_UCB0CLK_TA0.1_COMP0.0_A1-Pad13)") (class "Default")
      (node (ref "U1") (pin "13") (pinfunction "P1.1_UCB0CLK_TA0.1_COMP0.0_A1_13") (pintype "bidirectional"))
    )
    (net (code "70") (name "unconnected-(U1-P1.4_UCA0TXD_UCA0SIMO_TA1.2_TCK_A4_VREF+-Pad4)") (class "Default")
      (node (ref "U1") (pin "4") (pinfunction "P1.4_UCA0TXD_UCA0SIMO_TA1.2_TCK_A4_VREF+_4") (pintype "bidirectional"))
    )
    (net (code "71") (name "unconnected-(U1-P1.5_UCA0RXD_UCA0SOMI_TA1.1_TMS_A5-Pad5)") (class "Default")
      (node (ref "U1") (pin "5") (pinfunction "P1.5_UCA0RXD_UCA0SOMI_TA1.1_TMS_A5_5") (pintype "bidirectional"))
    )
    (net (code "72") (name "unconnected-(U1-P2.4_UCA1CLK_CAP1.1-Pad28)") (class "Default")
      (node (ref "U1") (pin "28") (pinfunction "P2.4_UCA1CLK_CAP1.1_28") (pintype "bidirectional"))
    )
    (net (code "73") (name "unconnected-(U1-P2.7_UCB1STE_CAP3.0-Pad36)") (class "Default")
      (node (ref "U1") (pin "36") (pinfunction "P2.7_UCB1STE_CAP3.0_36") (pintype "bidirectional"))
    )
    (net (code "74") (name "unconnected-(U1-P3.5_UCB1CLK_TB0TRG_CAP3.1-Pad37)") (class "Default")
      (node (ref "U1") (pin "37") (pinfunction "P3.5_UCB1CLK_TB0TRG_CAP3.1_37") (pintype "bidirectional"))
    )
    (net (code "75") (name "unconnected-(U1-P3.6_UCB1SOMI_UCB1SCL_CAP3.3-Pad39)") (class "Default")
      (node (ref "U1") (pin "39") (pinfunction "P3.6_UCB1SOMI_UCB1SCL_CAP3.3_39") (pintype "bidirectional"))
    )
    (net (code "76") (name "unconnected-(U1-P3.7_TA3.2_CAP2.0-Pad32)") (class "Default")
      (node (ref "U1") (pin "32") (pinfunction "P3.7_TA3.2_CAP2.0_32") (pintype "bidirectional"))
    )
    (net (code "77") (name "unconnected-(U1-P4.0_TA3.1_CAP2.1-Pad33)") (class "Default")
      (node (ref "U1") (pin "33") (pinfunction "P4.0_TA3.1_CAP2.1_33") (pintype "bidirectional"))
    )
    (net (code "78") (name "unconnected-(U1-P4.3_UCB1SOMI_UCB1SCL_TB0.5_A8-Pad8)") (class "Default")
      (node (ref "U1") (pin "8") (pinfunction "P4.3_UCB1SOMI_UCB1SCL_TB0.5_A8_8") (pintype "bidirectional"))
    )
    (net (code "79") (name "unconnected-(U1-P4.4_UCB1SIMO_UCB1SDA_TB0.6_A9-Pad9)") (class "Default")
      (node (ref "U1") (pin "9") (pinfunction "P4.4_UCB1SIMO_UCB1SDA_TB0.6_A9_9") (pintype "bidirectional"))
    )
    (net (code "80") (name "unconnected-(U1-P4.6_UCB0SIMO_UCB0SDA_TA3.1-Pad18)") (class "Default")
      (node (ref "U1") (pin "18") (pinfunction "P4.6_UCB0SIMO_UCB0SDA_TA3.1_18") (pintype "bidirectional"))
    )
    (net (code "81") (name "unconnected-(U1-P4.7_UCA0STE_TB0.1-Pad42)") (class "Default")
      (node (ref "U1") (pin "42") (pinfunction "P4.7_UCA0STE_TB0.1_42") (pintype "bidirectional"))
    )
    (net (code "82") (name "unconnected-(U1-P5.5_UCB0CLK_TA2CLK-Pad19)") (class "Default")
      (node (ref "U1") (pin "19") (pinfunction "P5.5_UCB0CLK_TA2CLK_19") (pintype "bidirectional"))
    )
    (net (code "83") (name "unconnected-(U1-VREG-Pad31)") (class "Default")
      (node (ref "U1") (pin "31") (pinfunction "VREG_31") (pintype "no_connect"))
    )
    (net (code "84") (name "unconnected-(U3-IO2-Pad2)") (class "Default")
      (node (ref "U3") (pin "2") (pinfunction "IO2_2") (pintype "bidirectional"))
    )
    (net (code "85") (name "unconnected-(U4-W-Pad6)") (class "Default")
      (node (ref "U4") (pin "6") (pinfunction "W_6") (pintype "output"))
    )
    (net (code "86") (name "unconnected-(U5-W-Pad6)") (class "Default")
      (node (ref "U5") (pin "6") (pinfunction "W_6") (pintype "output"))
    )
  )
)
